# EAX300_TesterControlBoard.net
KiCad netlist of a schematic drawn in Altium Designer
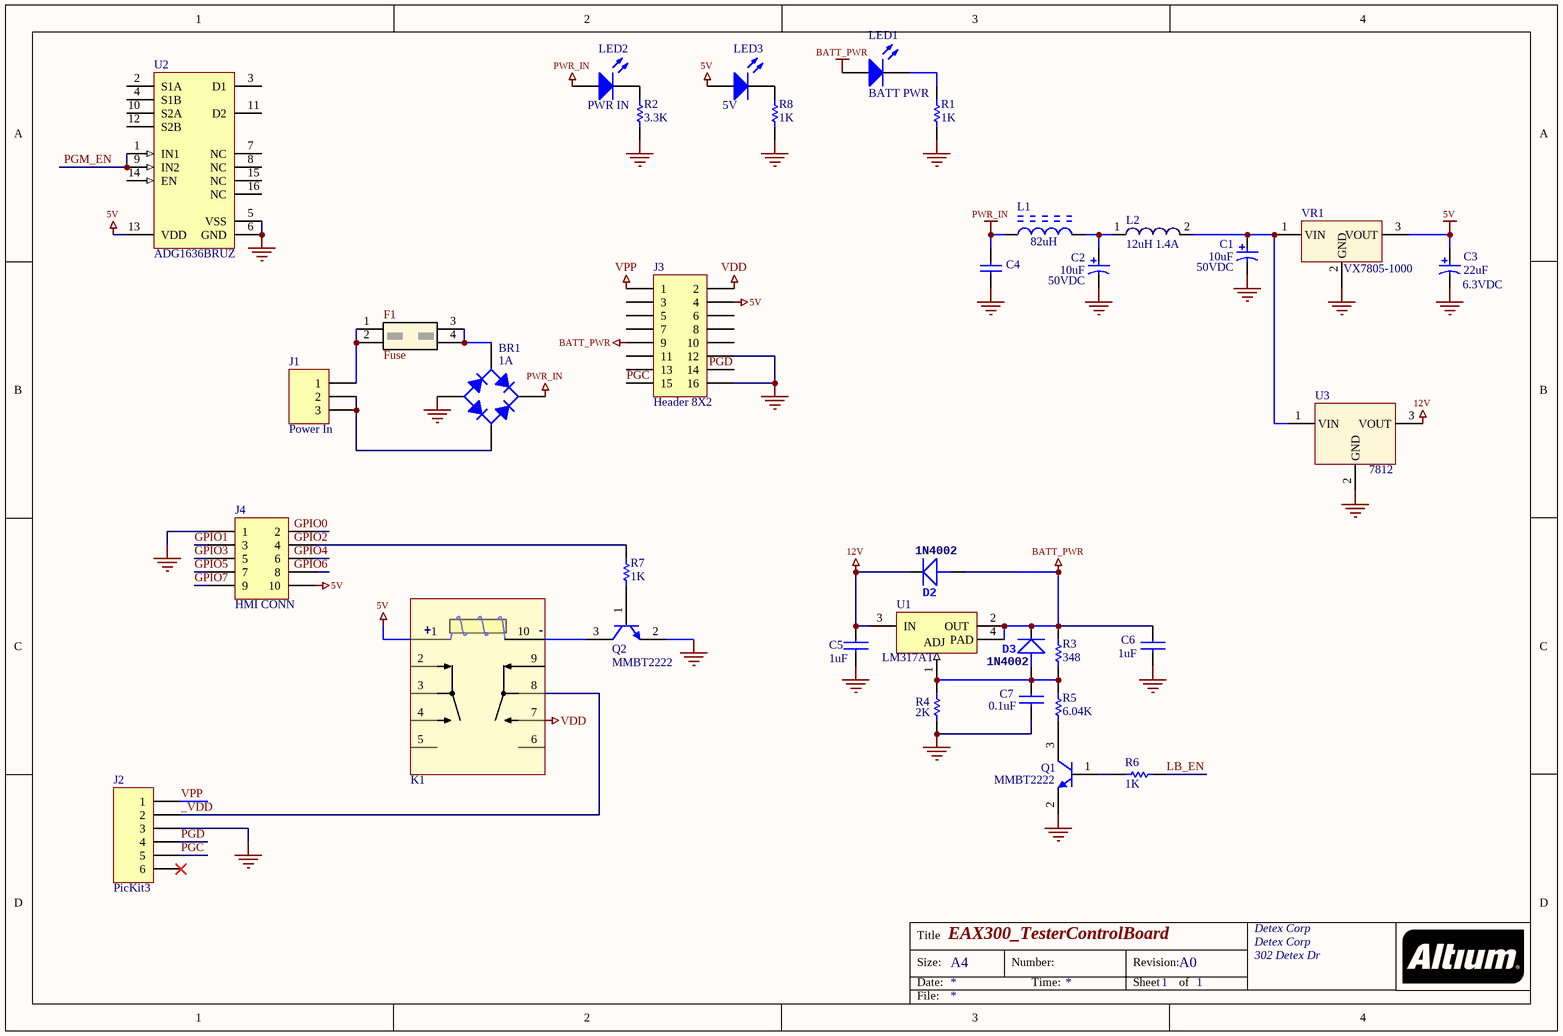
[diagram p0: EAX300_TesterControlBoard.SchDoc]

(export (version "E")
  (design (tool "Eeschema 10.0.6"))
  (components
    (comp (ref "BR1")
      (value "1A")
      (footprint "BRIDGE_1A_SMT")
      (description "Full Wave Diode Bridge")
      (fields (field (name "PUBLISHER") "Altium Limited"))
      (libsource (lib "Miscellaneous Devices") (part "Bridge1"))
    )
    (comp (ref "C1")
      (value "10uF")
      (footprint "KEMT-D-7343-31-2_M")
      (description "Capacitor, Tantalum, 10 uF, +/- 10%, 50 V, -55 to 125 degC, 2-Pin SMD, RoHS, Tape and Reel")
      (fields (field (name "VOLTAGE") "50VDC") (field (name "MFR") "AVR"))
      (libsource (lib "Altium Content Vault") (part "CAP-P-2"))
    )
    (comp (ref "C2")
      (value "10uF")
      (footprint "KEMT-D-7343-31-2_M")
      (description "Capacitor, Tantalum, 10 uF, +/- 10%, 50 V, -55 to 125 degC, 2-Pin SMD, RoHS, Tape and Reel")
      (fields (field (name "VOLTAGE") "50VDC") (field (name "MFR") "AVR"))
      (libsource (lib "Altium Content Vault") (part "CAP-P-2"))
    )
    (comp (ref "C3")
      (value "22uF")
      (footprint "KEMT-D-7343-31-2_M")
      (description "Capacitor, Tantalum, 22 uF, +/- 10%, 6.3V, -55 to 125 degC, 2-Pin SMD, RoHS, Tape and Reel")
      (fields
        (field (name "VOLTAGE") "6.3VDC")
        (field (name "MANUFACTURER") "Kemet")
        (field (name "MFR") "AVX")
      )
      (libsource (lib "Altium Content Vault") (part "CAP-P-2"))
    )
    (comp (ref "C4")
      (value "B72220S1300K102")
      (footprint "TDK-S20K275")
      (description "Leaded Varistor, 850 pF, 275 Vrms, 8 KA, -40 to 85 degC, 2-Pin THD, RoHS, Bulk")
      (fields (field (name "MFR") "TDK"))
      (libsource (lib "Altium Content Vault") (part "CAP-NP-2"))
    )
    (comp (ref "C5")
      (value "1uF")
      (footprint "CAPC0805(2012)75_N")
      (description "CAP CER 1UF 50V X7R 0805")
      (fields
        (field (name "MANUFACTURER") "Murata Electronics North America")
        (field (name "MANUFACTURER PART NUMBER") "GRM21BR71H105KA12L")
      )
      (libsource (lib "iMX6 Rex Development Baseboard V1I1") (part "GRM21BR71H105KA12L"))
    )
    (comp (ref "C6")
      (value "1uF")
      (footprint "CAPC0805(2012)75_N")
      (description "CAP CER 1UF 50V X7R 0805")
      (fields
        (field (name "MANUFACTURER") "Murata Electronics North America")
        (field (name "MANUFACTURER PART NUMBER") "GRM21BR71H105KA12L")
      )
      (libsource (lib "iMX6 Rex Development Baseboard V1I1") (part "GRM21BR71H105KA12L"))
    )
    (comp (ref "C7")
      (value "0.1uF")
      (footprint "CAPC0805(2012)75_N")
      (description "CAP CER 1UF 50V X7R 0805")
      (fields
        (field (name "MANUFACTURER") "Murata Electronics North America")
        (field (name "MANUFACTURER PART NUMBER") "GRM21BR71H105KA12L")
      )
      (libsource (lib "iMX6 Rex Development Baseboard V1I1") (part "GRM21BR71H105KA12L"))
    )
    (comp (ref "D2")
      (value "1N4002")
      (footprint "DO-214AC")
      (description "1N4004SMT")
      (libsource (lib "AltiumIntegratedLibrary") (part "1N4004SMT"))
    )
    (comp (ref "D3")
      (value "1N4002")
      (footprint "DO-214AC")
      (description "1N4004SMT")
      (libsource (lib "AltiumIntegratedLibrary") (part "1N4004SMT"))
    )
    (comp (ref "F1")
      (value "PC Auto Fuse Holder")
      (footprint "AUTO-FUSE HOLDER")
      (description "Fuse Holder 2 IN 1 AUTO BLDE HOLDER")
      (fields
        (field (name "MPN") "3587-10")
        (field (name "MFR") "Keystone Electronics")
        (field (name "AMPERAGE") "Fuse")
      )
      (libsource (lib "EAX300_TesterControlBoard") (part "PC Auto Fuse Holder"))
    )
    (comp (ref "J1")
      (value "Power In")
      (footprint "KLD-0202_2")
      (description "Header, 3-Pin")
      (fields (field (name "PUBLISHER") "Altium Limited"))
      (libsource (lib "Miscellaneous Connectors") (part "Header 3"))
    )
    (comp (ref "J2")
      (value "PicKit3")
      (footprint "HDR1X6")
      (description "PicKit3 Connector")
      (libsource (lib "Miscellaneous Connectors") (part "Header 6"))
    )
    (comp (ref "J3")
      (value "Header 8X2")
      (footprint "HDR2X8")
      (description "Header, 8-Pin, Dual row")
      (fields (field (name "PUBLISHER") "Altium Limited"))
      (libsource (lib "Miscellaneous Connectors") (part "Header 8X2"))
    )
    (comp (ref "J4")
      (value "HMI CONN")
      (footprint "HDR2X5")
      (description "Header, 5-Pin, Dual row")
      (fields (field (name "PUBLISHER") "Altium Limited"))
      (libsource (lib "Miscellaneous Connectors") (part "Header 5X2"))
    )
    (comp (ref "K1")
      (value "QW POWER")
      (footprint "AZ_940")
      (description "AZ850-5")
      (fields (field (name "PART NUMBER") "101671"))
      (libsource (lib "105848_revD3") (part "Relay_1"))
    )
    (comp (ref "L1")
      (value "82uH")
      (footprint "BOUR-SRR1280-2_V")
      (description "Shielded SMD Power Inductor, 82 uH, +/- 20%, -40 to 125 degC, 2-Pin SMD, RoHS, Tape and Reel")
      (fields (field (name "MFR") "Bourns") (field (name "TOLERANCE") "20%"))
      (libsource (lib "Altium Content Vault") (part "IND-FERR-2"))
    )
    (comp (ref "L2")
      (value "12uH 1.4A")
      (footprint "WE-LQS 4018")
      (description "SMD Power Inductor, L=12 µH")
      (fields (field (name "MFR") "Bourns"))
      (libsource (lib "Altium Content Vault") (part "WE-IND-INDUCTOR-2"))
    )
    (comp (ref "LED1")
      (value "BATT PWR")
      (footprint "LED_1206_2")
      (description "Typical BLUE SiC LED")
      (fields (field (name "PUBLISHER") "Altium Limited"))
      (libsource (lib "Miscellaneous Devices") (part "LED3"))
    )
    (comp (ref "LED2")
      (value "PWR IN")
      (footprint "LED_1206_2")
      (description "Typical BLUE SiC LED")
      (fields (field (name "PUBLISHER") "Altium Limited"))
      (libsource (lib "Miscellaneous Devices") (part "LED3"))
    )
    (comp (ref "LED3")
      (value "5V")
      (footprint "LED_1206_2")
      (description "Typical BLUE SiC LED")
      (fields (field (name "PUBLISHER") "Altium Limited"))
      (libsource (lib "Miscellaneous Devices") (part "LED3"))
    )
    (comp (ref "Q1")
      (value "MMBT2222")
      (footprint "ONSC-SOT-23-3-318-08_V")
      (description "General Purpose Transistor, NPN Silicon, 3-Pin SOT-23, Pb-Free, Tape and Reel")
      (fields (field (name "PARTNUMBER") "MMBT2222LT1G") (field (name "MANUFACTURER") "On Semiconductor"))
      (libsource (lib "Altium Content Vault") (part "ONSC-NPN-B1E2C3-3"))
    )
    (comp (ref "Q2")
      (value "MMBT2222")
      (footprint "ONSC-SOT-23-3-318-08_V")
      (description "General Purpose Transistor, NPN Silicon, 3-Pin SOT-23, Pb-Free, Tape and Reel")
      (fields (field (name "PARTNUMBER") "MMBT2222LT1G") (field (name "MANUFACTURER") "On Semiconductor"))
      (libsource (lib "Altium Content Vault") (part "ONSC-NPN-B1E2C3-3"))
    )
    (comp (ref "R1")
      (value "1K")
      (footprint "RES_0805")
      (description "Semiconductor Resistor")
      (fields (field (name "Comment") "0805") (field (name "PUBLISHER") "Altium Limited"))
      (libsource (lib "Miscellaneous Devices") (part "Res Semi"))
    )
    (comp (ref "R2")
      (value "3.3K")
      (footprint "RES_0805")
      (description "Semiconductor Resistor")
      (fields (field (name "Comment") "0805") (field (name "PUBLISHER") "Altium Limited"))
      (libsource (lib "Miscellaneous Devices") (part "Res Semi"))
    )
    (comp (ref "R3")
      (value "348")
      (footprint "RES_0805")
      (description "Semiconductor Resistor")
      (fields (field (name "Comment") "0805") (field (name "PUBLISHER") "Altium Limited"))
      (libsource (lib "Miscellaneous Devices") (part "Res Semi"))
    )
    (comp (ref "R4")
      (value "2K")
      (footprint "RES_0805")
      (description "Semiconductor Resistor")
      (fields (field (name "Comment") "0805") (field (name "PUBLISHER") "Altium Limited"))
      (libsource (lib "Miscellaneous Devices") (part "Res Semi"))
    )
    (comp (ref "R5")
      (value "6.04K")
      (footprint "RES_0805")
      (description "Semiconductor Resistor")
      (fields (field (name "Comment") "0805") (field (name "PUBLISHER") "Altium Limited"))
      (libsource (lib "Miscellaneous Devices") (part "Res Semi"))
    )
    (comp (ref "R6")
      (value "1K")
      (footprint "RES_0805")
      (description "Semiconductor Resistor")
      (fields (field (name "Comment") "0805") (field (name "PUBLISHER") "Altium Limited"))
      (libsource (lib "Miscellaneous Devices") (part "Res Semi"))
    )
    (comp (ref "R7")
      (value "1K")
      (footprint "RES_0805")
      (description "Semiconductor Resistor")
      (fields (field (name "Comment") "0805") (field (name "PUBLISHER") "Altium Limited"))
      (libsource (lib "Miscellaneous Devices") (part "Res Semi"))
    )
    (comp (ref "R8")
      (value "1K")
      (footprint "RES_0805")
      (description "Semiconductor Resistor")
      (fields (field (name "Comment") "0805") (field (name "PUBLISHER") "Altium Limited"))
      (libsource (lib "Miscellaneous Devices") (part "Res Semi"))
    )
    (comp (ref "U1")
      (value "LM317AT")
      (footprint "SOT223_M")
      (description "3-Terminal Adjustable Regulator, 3-pin TO-220, Pb-Free")
      (fields (field (name "MFR") "ON Semiconductor"))
      (libsource (lib "EAX300_TesterControlBoard") (part "LM317"))
    )
    (comp (ref "U2")
      (value "ADG1636BRUZ")
      (footprint "ADI-RU-16_N")
      (fields (field (name "MANUFACTURER") "Analog Devices"))
      (libsource (lib "Altium Content Vault") (part "ADI-ADG1636-RU-16"))
    )
    (comp (ref "U3")
      (value "7812")
      (footprint "7812")
      (libsource (lib "EAX300_TesterControlBoard") (part "7812"))
    )
    (comp (ref "VR1")
      (value "VX7805-1000")
      (footprint "78xx")
      (description "Non-Isolated DC Switching Regulator")
      (fields (field (name "MFR") "CUI, Inc."))
      (libsource (lib "EAX300_TesterControlBoard") (part "VX78xx"))
    )
  )
  (nets
    (net (code "1") (name "/GPIO0") (class "Default")
      (node (ref "J4") (pin "2") (pinfunction "2_2") (pintype "passive"))
    )
    (net (code "2") (name "/GPIO1") (class "Default")
      (node (ref "J4") (pin "3") (pinfunction "3_3") (pintype "passive"))
    )
    (net (code "3") (name "/GPIO2") (class "Default")
      (node (ref "J4") (pin "4") (pinfunction "4_4") (pintype "passive"))
      (node (ref "R7") (pin "1") (pinfunction "1_1") (pintype "passive"))
    )
    (net (code "4") (name "/GPIO3") (class "Default")
      (node (ref "J4") (pin "5") (pinfunction "5_5") (pintype "passive"))
    )
    (net (code "5") (name "/GPIO4") (class "Default")
      (node (ref "J4") (pin "6") (pinfunction "6_6") (pintype "passive"))
    )
    (net (code "6") (name "/GPIO5") (class "Default")
      (node (ref "J4") (pin "7") (pinfunction "7_7") (pintype "passive"))
    )
    (net (code "7") (name "/GPIO6") (class "Default")
      (node (ref "J4") (pin "8") (pinfunction "8_8") (pintype "passive"))
    )
    (net (code "8") (name "/GPIO7") (class "Default")
      (node (ref "J4") (pin "9") (pinfunction "9_9") (pintype "passive"))
    )
    (net (code "9") (name "/LB_EN") (class "Default")
      (node (ref "R6") (pin "1") (pinfunction "1_1") (pintype "passive"))
    )
    (net (code "10") (name "/PGC") (class "Default")
      (node (ref "J2") (pin "5") (pinfunction "5_5") (pintype "passive"))
      (node (ref "J3") (pin "15") (pinfunction "15_15") (pintype "passive"))
    )
    (net (code "11") (name "/PGD") (class "Default")
      (node (ref "J2") (pin "4") (pinfunction "4_4") (pintype "passive"))
      (node (ref "J3") (pin "14") (pinfunction "14_14") (pintype "passive"))
    )
    (net (code "12") (name "/PGM_EN") (class "Default")
      (node (ref "U2") (pin "1") (pinfunction "IN1_1") (pintype "input"))
      (node (ref "U2") (pin "9") (pinfunction "IN2_9") (pintype "input"))
    )
    (net (code "13") (name "/_VDD") (class "Default")
      (node (ref "J2") (pin "2") (pinfunction "2_2") (pintype "passive"))
      (node (ref "K1") (pin "8") (pinfunction "COM_8") (pintype "passive"))
    )
    (net (code "14") (name "5V") (class "Default")
      (node (ref "C3") (pin "1") (pinfunction "1_1") (pintype "passive"))
      (node (ref "J3") (pin "4") (pinfunction "4_4") (pintype "passive"))
      (node (ref "J4") (pin "10") (pinfunction "10_10") (pintype "passive"))
      (node (ref "K1") (pin "1") (pinfunction "V+_1") (pintype "passive"))
      (node (ref "LED3") (pin "1") (pinfunction "A_1") (pintype "passive"))
      (node (ref "U2") (pin "13") (pinfunction "VDD_13") (pintype "power_in"))
      (node (ref "VR1") (pin "3") (pinfunction "VOUT_3") (pintype "passive"))
    )
    (net (code "15") (name "12V") (class "Default")
      (node (ref "C5") (pin "1") (pinfunction "1_1") (pintype "passive"))
      (node (ref "D2") (pin "2") (pinfunction "2_2") (pintype "passive"))
      (node (ref "U1") (pin "3") (pinfunction "IN_3") (pintype "power_in"))
      (node (ref "U3") (pin "3") (pinfunction "VOUT_3") (pintype "passive"))
    )
    (net (code "16") (name "BATT_PWR") (class "Default")
      (node (ref "C6") (pin "1") (pinfunction "1_1") (pintype "passive"))
      (node (ref "D2") (pin "1") (pinfunction "1_1") (pintype "passive"))
      (node (ref "D3") (pin "2") (pinfunction "2_2") (pintype "passive"))
      (node (ref "J3") (pin "9") (pinfunction "9_9") (pintype "passive"))
      (node (ref "LED1") (pin "1") (pinfunction "A_1") (pintype "passive"))
      (node (ref "R3") (pin "2") (pinfunction "2_2") (pintype "passive"))
      (node (ref "U1") (pin "2") (pinfunction "OUT_2") (pintype "power_in"))
      (node (ref "U1") (pin "4") (pinfunction "PAD_4") (pintype "power_in"))
    )
    (net (code "17") (name "GND") (class "Default")
      (node (ref "BR1") (pin "3") (pinfunction "A_3") (pintype "passive"))
      (node (ref "C1") (pin "2") (pinfunction "2_2") (pintype "passive"))
      (node (ref "C2") (pin "2") (pinfunction "2_2") (pintype "passive"))
      (node (ref "C3") (pin "2") (pinfunction "2_2") (pintype "passive"))
      (node (ref "C4") (pin "2") (pinfunction "2_2") (pintype "passive"))
      (node (ref "C5") (pin "2") (pinfunction "2_2") (pintype "passive"))
      (node (ref "C6") (pin "2") (pinfunction "2_2") (pintype "passive"))
      (node (ref "C7") (pin "2") (pinfunction "2_2") (pintype "passive"))
      (node (ref "J2") (pin "3") (pinfunction "3_3") (pintype "passive"))
      (node (ref "J3") (pin "12") (pinfunction "12_12") (pintype "passive"))
      (node (ref "J3") (pin "16") (pinfunction "16_16") (pintype "passive"))
      (node (ref "J4") (pin "1") (pinfunction "1_1") (pintype "passive"))
      (node (ref "Q1") (pin "2") (pinfunction "E_2") (pintype "passive"))
      (node (ref "Q2") (pin "2") (pinfunction "E_2") (pintype "passive"))
      (node (ref "R1") (pin "1") (pinfunction "1_1") (pintype "passive"))
      (node (ref "R2") (pin "2") (pinfunction "2_2") (pintype "passive"))
      (node (ref "R4") (pin "1") (pinfunction "1_1") (pintype "passive"))
      (node (ref "R8") (pin "1") (pinfunction "1_1") (pintype "passive"))
      (node (ref "U2") (pin "5") (pinfunction "VSS_5") (pintype "power_in"))
      (node (ref "U2") (pin "6") (pinfunction "GND_6") (pintype "power_in"))
      (node (ref "U3") (pin "2") (pinfunction "GND_2") (pintype "passive"))
      (node (ref "VR1") (pin "2") (pinfunction "GND_2") (pintype "passive"))
    )
    (net (code "18") (name "Net-(BR1-C-Pad2)") (class "Default")
      (node (ref "BR1") (pin "2") (pinfunction "C_2") (pintype "passive"))
      (node (ref "J1") (pin "2") (pinfunction "2_2") (pintype "passive"))
      (node (ref "J1") (pin "3") (pinfunction "3_3") (pintype "passive"))
    )
    (net (code "19") (name "Net-(BR1-C-Pad4)") (class "Default")
      (node (ref "BR1") (pin "4") (pinfunction "C_4") (pintype "passive"))
      (node (ref "F1") (pin "3") (pinfunction "3_3") (pintype "passive"))
      (node (ref "F1") (pin "4") (pinfunction "4_4") (pintype "passive"))
    )
    (net (code "20") (name "Net-(C2-Pad1)") (class "Default")
      (node (ref "C2") (pin "1") (pinfunction "1_1") (pintype "passive"))
      (node (ref "L1") (pin "2") (pinfunction "2_2") (pintype "passive"))
      (node (ref "L2") (pin "1") (pinfunction "1_1") (pintype "passive"))
    )
    (net (code "21") (name "Net-(F1-Pad1)") (class "Default")
      (node (ref "F1") (pin "1") (pinfunction "1_1") (pintype "passive"))
      (node (ref "F1") (pin "2") (pinfunction "2_2") (pintype "passive"))
      (node (ref "J1") (pin "1") (pinfunction "1_1") (pintype "passive"))
    )
    (net (code "22") (name "Net-(K1-V-)") (class "Default")
      (node (ref "K1") (pin "10") (pinfunction "V-_10") (pintype "passive"))
      (node (ref "Q2") (pin "3") (pinfunction "C_3") (pintype "passive"))
    )
    (net (code "23") (name "Net-(LED1-K)") (class "Default")
      (node (ref "LED1") (pin "2") (pinfunction "K_2") (pintype "passive"))
      (node (ref "R1") (pin "2") (pinfunction "2_2") (pintype "passive"))
    )
    (net (code "24") (name "Net-(LED2-K)") (class "Default")
      (node (ref "LED2") (pin "2") (pinfunction "K_2") (pintype "passive"))
      (node (ref "R2") (pin "1") (pinfunction "1_1") (pintype "passive"))
    )
    (net (code "25") (name "Net-(LED3-K)") (class "Default")
      (node (ref "LED3") (pin "2") (pinfunction "K_2") (pintype "passive"))
      (node (ref "R8") (pin "2") (pinfunction "2_2") (pintype "passive"))
    )
    (net (code "26") (name "Net-(Q1-B)") (class "Default")
      (node (ref "Q1") (pin "1") (pinfunction "B_1") (pintype "passive"))
      (node (ref "R6") (pin "2") (pinfunction "2_2") (pintype "passive"))
    )
    (net (code "27") (name "Net-(Q1-C)") (class "Default")
      (node (ref "Q1") (pin "3") (pinfunction "C_3") (pintype "passive"))
      (node (ref "R5") (pin "1") (pinfunction "1_1") (pintype "passive"))
    )
    (net (code "28") (name "Net-(Q2-B)") (class "Default")
      (node (ref "Q2") (pin "1") (pinfunction "B_1") (pintype "passive"))
      (node (ref "R7") (pin "2") (pinfunction "2_2") (pintype "passive"))
    )
    (net (code "29") (name "Net-(U1-ADJ)") (class "Default")
      (node (ref "C7") (pin "1") (pinfunction "1_1") (pintype "passive"))
      (node (ref "D3") (pin "1") (pinfunction "1_1") (pintype "passive"))
      (node (ref "R3") (pin "1") (pinfunction "1_1") (pintype "passive"))
      (node (ref "R4") (pin "2") (pinfunction "2_2") (pintype "passive"))
      (node (ref "R5") (pin "2") (pinfunction "2_2") (pintype "passive"))
      (node (ref "U1") (pin "1") (pinfunction "ADJ_1") (pintype "input"))
    )
    (net (code "30") (name "Net-(U3-VIN)") (class "Default")
      (node (ref "C1") (pin "1") (pinfunction "1_1") (pintype "passive"))
      (node (ref "L2") (pin "2") (pinfunction "2_2") (pintype "passive"))
      (node (ref "U3") (pin "1") (pinfunction "VIN_1") (pintype "passive"))
      (node (ref "VR1") (pin "1") (pinfunction "VIN_1") (pintype "passive"))
    )
    (net (code "31") (name "PWR_IN") (class "Default")
      (node (ref "BR1") (pin "1") (pinfunction "K_1") (pintype "passive"))
      (node (ref "C4") (pin "1") (pinfunction "1_1") (pintype "passive"))
      (node (ref "L1") (pin "1") (pinfunction "1_1") (pintype "passive"))
      (node (ref "LED2") (pin "1") (pinfunction "A_1") (pintype "passive"))
    )
    (net (code "32") (name "VDD") (class "Default")
      (node (ref "J3") (pin "2") (pinfunction "2_2") (pintype "passive"))
      (node (ref "K1") (pin "7") (pinfunction "N/O_7") (pintype "passive"))
    )
    (net (code "33") (name "VPP") (class "Default")
      (node (ref "J2") (pin "1") (pinfunction "1_1") (pintype "passive"))
      (node (ref "J3") (pin "1") (pinfunction "1_1") (pintype "passive"))
    )
    (net (code "34") (name "unconnected-(J2-Pad6)") (class "Default")
      (node (ref "J2") (pin "6") (pinfunction "6_6") (pintype "passive+no_connect"))
    )
    (net (code "35") (name "unconnected-(J3-Pad3)") (class "Default")
      (node (ref "J3") (pin "3") (pinfunction "3_3") (pintype "passive"))
    )
    (net (code "36") (name "unconnected-(J3-Pad5)") (class "Default")
      (node (ref "J3") (pin "5") (pinfunction "5_5") (pintype "passive"))
    )
    (net (code "37") (name "unconnected-(J3-Pad6)") (class "Default")
      (node (ref "J3") (pin "6") (pinfunction "6_6") (pintype "passive"))
    )
    (net (code "38") (name "unconnected-(J3-Pad7)") (class "Default")
      (node (ref "J3") (pin "7") (pinfunction "7_7") (pintype "passive"))
    )
    (net (code "39") (name "unconnected-(J3-Pad8)") (class "Default")
      (node (ref "J3") (pin "8") (pinfunction "8_8") (pintype "passive"))
    )
    (net (code "40") (name "unconnected-(J3-Pad10)") (class "Default")
      (node (ref "J3") (pin "10") (pinfunction "10_10") (pintype "passive"))
    )
    (net (code "41") (name "unconnected-(J3-Pad11)") (class "Default")
      (node (ref "J3") (pin "11") (pinfunction "11_11") (pintype "passive"))
    )
    (net (code "42") (name "unconnected-(J3-Pad13)") (class "Default")
      (node (ref "J3") (pin "13") (pinfunction "13_13") (pintype "passive"))
    )
    (net (code "43") (name "unconnected-(K1-COM-Pad3)") (class "Default")
      (node (ref "K1") (pin "3") (pinfunction "COM_3") (pintype "passive"))
    )
    (net (code "44") (name "unconnected-(K1-N{slash}C-Pad2)") (class "Default")
      (node (ref "K1") (pin "2") (pinfunction "N/C_2") (pintype "passive"))
    )
    (net (code "45") (name "unconnected-(K1-N{slash}C-Pad9)") (class "Default")
      (node (ref "K1") (pin "9") (pinfunction "N/C_9") (pintype "passive"))
    )
    (net (code "46") (name "unconnected-(K1-N{slash}O-Pad4)") (class "Default")
      (node (ref "K1") (pin "4") (pinfunction "N/O_4") (pintype "passive"))
    )
    (net (code "47") (name "unconnected-(K1-Pad5)") (class "Default")
      (node (ref "K1") (pin "5") (pintype "passive"))
    )
    (net (code "48") (name "unconnected-(K1-Pad6)") (class "Default")
      (node (ref "K1") (pin "6") (pintype "passive"))
    )
    (net (code "49") (name "unconnected-(U2-D1-Pad3)") (class "Default")
      (node (ref "U2") (pin "3") (pinfunction "D1_3") (pintype "passive"))
    )
    (net (code "50") (name "unconnected-(U2-D2-Pad11)") (class "Default")
      (node (ref "U2") (pin "11") (pinfunction "D2_11") (pintype "passive"))
    )
    (net (code "51") (name "unconnected-(U2-EN-Pad14)") (class "Default")
      (node (ref "U2") (pin "14") (pinfunction "EN_14") (pintype "input"))
    )
    (net (code "52") (name "unconnected-(U2-NC-Pad7)") (class "Default")
      (node (ref "U2") (pin "7") (pinfunction "NC_7") (pintype "passive"))
    )
    (net (code "53") (name "unconnected-(U2-NC-Pad8)") (class "Default")
      (node (ref "U2") (pin "8") (pinfunction "NC_8") (pintype "passive"))
    )
    (net (code "54") (name "unconnected-(U2-NC-Pad15)") (class "Default")
      (node (ref "U2") (pin "15") (pinfunction "NC_15") (pintype "passive"))
    )
    (net (code "55") (name "unconnected-(U2-NC-Pad16)") (class "Default")
      (node (ref "U2") (pin "16") (pinfunction "NC_16") (pintype "passive"))
    )
    (net (code "56") (name "unconnected-(U2-S1A-Pad2)") (class "Default")
      (node (ref "U2") (pin "2") (pinfunction "S1A_2") (pintype "passive"))
    )
    (net (code "57") (name "unconnected-(U2-S1B-Pad4)") (class "Default")
      (node (ref "U2") (pin "4") (pinfunction "S1B_4") (pintype "passive"))
    )
    (net (code "58") (name "unconnected-(U2-S2A-Pad10)") (class "Default")
      (node (ref "U2") (pin "10") (pinfunction "S2A_10") (pintype "passive"))
    )
    (net (code "59") (name "unconnected-(U2-S2B-Pad12)") (class "Default")
      (node (ref "U2") (pin "12") (pinfunction "S2B_12") (pintype "passive"))
    )
  )
)
